# TYPEC.net
KiCad netlist of a schematic drawn in Altium Designer
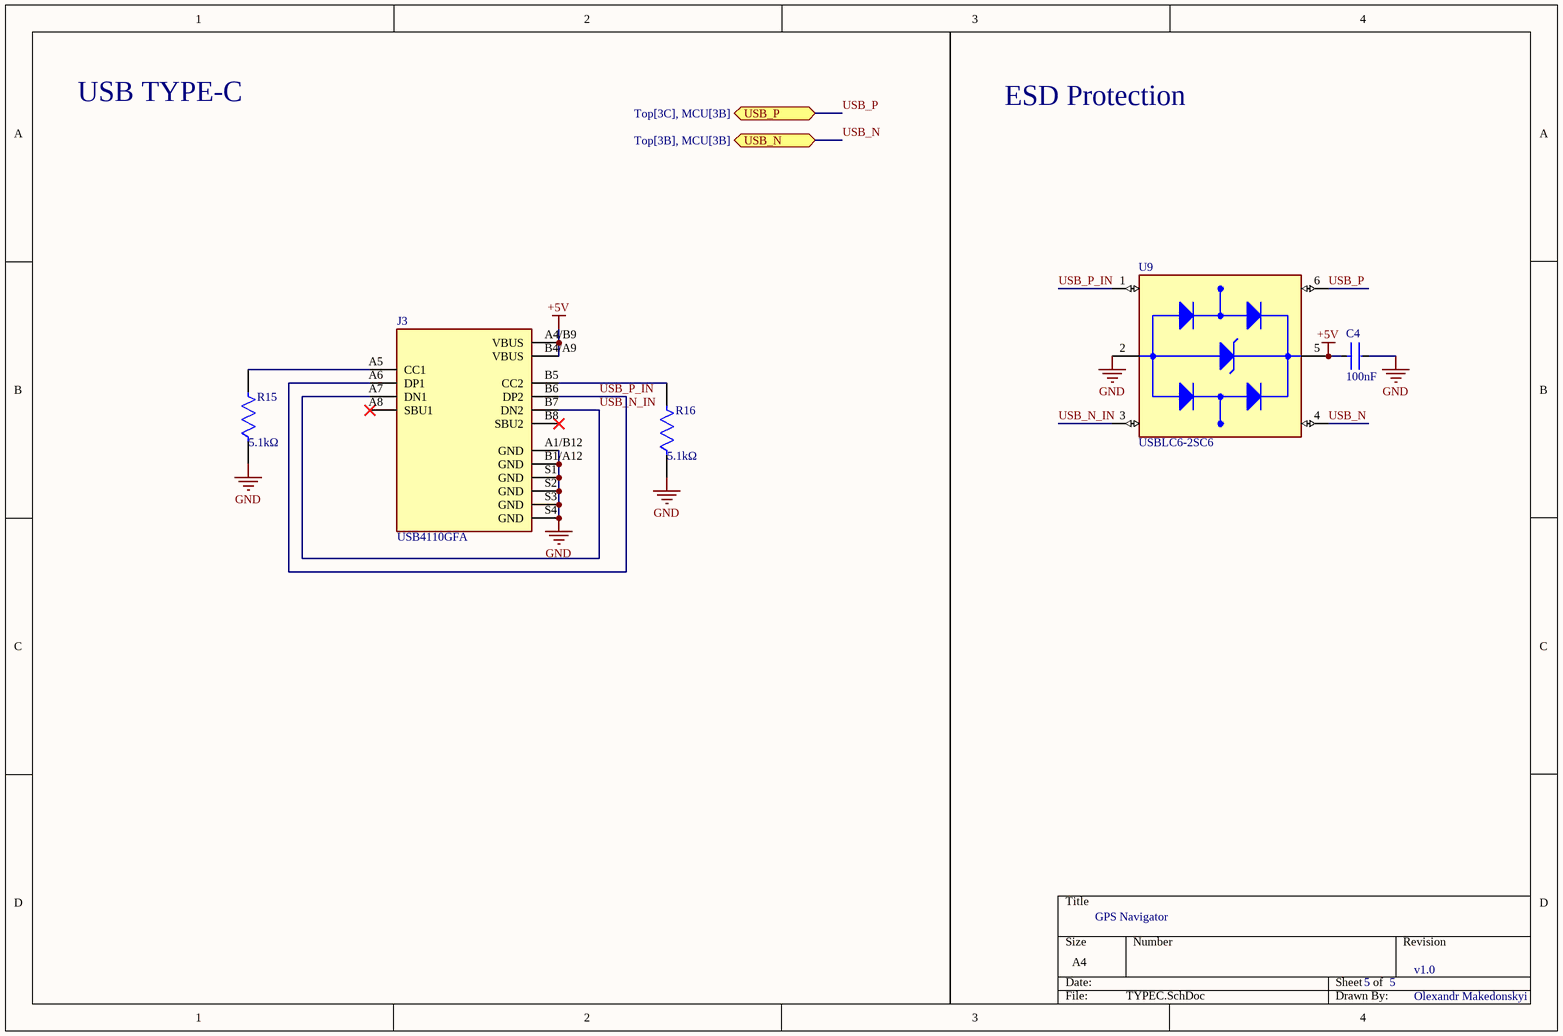
[diagram p0: TYPEC.SchDoc]

(export (version "E")
  (design (tool "Eeschema 10.0.6"))
  (components
    (comp (ref "C4")
      (value "100nF")
      (footprint "0402_CAPACITOR")
      (libsource (lib "Olexandr Makedonskyi") (part "CAPACITOR"))
    )
    (comp (ref "J3")
      (value "USB4110GFA")
      (footprint "gps_project_pcb_library:GCT_USB4110GFA")
      (fields (field (name "MF") "Global Connector Technology"))
      (libsource (lib "gps_project_schematic_library") (part "USB4110GFA"))
    )
    (comp (ref "R15")
      (value "5.1kΩ")
      (footprint "0402_RESISTOR")
      (fields (field (name "Comment") "RESISTOR"))
      (libsource (lib "gps_project_schematic_library") (part "RESISTOR"))
    )
    (comp (ref "R16")
      (value "5.1kΩ")
      (footprint "gps_project_pcb_library:0603_RESISTOR")
      (fields (field (name "Comment") "RESISTOR"))
      (libsource (lib "gps_project_schematic_library") (part "RESISTOR"))
    )
    (comp (ref "U9")
      (value "USBLC6-2SC6")
      (footprint "gps_project_pcb_library:SOT95P280X145-6N")
      (description "17V Clamp 5A (8/20Âµs) Ipp Tvs Diode Surface Mount SOT-23-6")
      (fields (field (name "MF") "STMicroelectronics"))
      (libsource (lib "gps_project_schematic_library") (part "USBLC6-2SC6"))
    )
  )
  (nets
    (net (code "1") (name "+5V") (class "Default")
      (node (ref "C4") (pin "1") (pinfunction "1_1") (pintype "passive"))
      (node (ref "J3") (pin "A4/B9") (pinfunction "VBUS_A4/B9") (pintype "passive"))
      (node (ref "J3") (pin "B4/A9") (pinfunction "VBUS_B4/A9") (pintype "passive"))
      (node (ref "U9") (pin "5") (pinfunction "VBUS_5") (pintype "power_in"))
    )
    (net (code "2") (name "/USB_N") (class "Default")
      (node (ref "U9") (pin "4") (pinfunction "I/O2_OUT_4") (pintype "bidirectional"))
    )
    (net (code "3") (name "/USB_N_IN") (class "Default")
      (node (ref "J3") (pin "A7") (pinfunction "DN1_A7") (pintype "passive"))
      (node (ref "J3") (pin "B7") (pinfunction "DN2_B7") (pintype "passive"))
      (node (ref "U9") (pin "3") (pinfunction "I/O2_IN_3") (pintype "bidirectional"))
    )
    (net (code "4") (name "/USB_P") (class "Default")
      (node (ref "U9") (pin "6") (pinfunction "I/O1_OUT_6") (pintype "bidirectional"))
    )
    (net (code "5") (name "/USB_P_IN") (class "Default")
      (node (ref "J3") (pin "A6") (pinfunction "DP1_A6") (pintype "passive"))
      (node (ref "J3") (pin "B6") (pinfunction "DP2_B6") (pintype "passive"))
      (node (ref "U9") (pin "1") (pinfunction "I/O1_IN_1") (pintype "bidirectional"))
    )
    (net (code "6") (name "GND") (class "Default")
      (node (ref "C4") (pin "2") (pinfunction "2_2") (pintype "passive"))
      (node (ref "J3") (pin "A1/B12") (pinfunction "GND_A1/B12") (pintype "passive"))
      (node (ref "J3") (pin "B1/A12") (pinfunction "GND_B1/A12") (pintype "passive"))
      (node (ref "J3") (pin "S1") (pinfunction "GND_S1") (pintype "passive"))
      (node (ref "J3") (pin "S2") (pinfunction "GND_S2") (pintype "passive"))
      (node (ref "J3") (pin "S3") (pinfunction "GND_S3") (pintype "passive"))
      (node (ref "J3") (pin "S4") (pinfunction "GND_S4") (pintype "passive"))
      (node (ref "R15") (pin "1") (pinfunction "1_1") (pintype "passive"))
      (node (ref "R16") (pin "1") (pinfunction "1_1") (pintype "passive"))
      (node (ref "U9") (pin "2") (pinfunction "GND_2") (pintype "power_in"))
    )
    (net (code "7") (name "Net-(J3-CC1)") (class "Default")
      (node (ref "J3") (pin "A5") (pinfunction "CC1_A5") (pintype "passive"))
      (node (ref "R15") (pin "2") (pinfunction "2_2") (pintype "passive"))
    )
    (net (code "8") (name "Net-(J3-CC2)") (class "Default")
      (node (ref "J3") (pin "B5") (pinfunction "CC2_B5") (pintype "passive"))
      (node (ref "R16") (pin "2") (pinfunction "2_2") (pintype "passive"))
    )
    (net (code "9") (name "unconnected-(J3-SBU1-PadA8)") (class "Default")
      (node (ref "J3") (pin "A8") (pinfunction "SBU1_A8") (pintype "passive+no_connect"))
    )
    (net (code "10") (name "unconnected-(J3-SBU2-PadB8)") (class "Default")
      (node (ref "J3") (pin "B8") (pinfunction "SBU2_B8") (pintype "passive+no_connect"))
    )
  )
)
